# CAN.net
KiCad netlist of a schematic drawn in Altium Designer
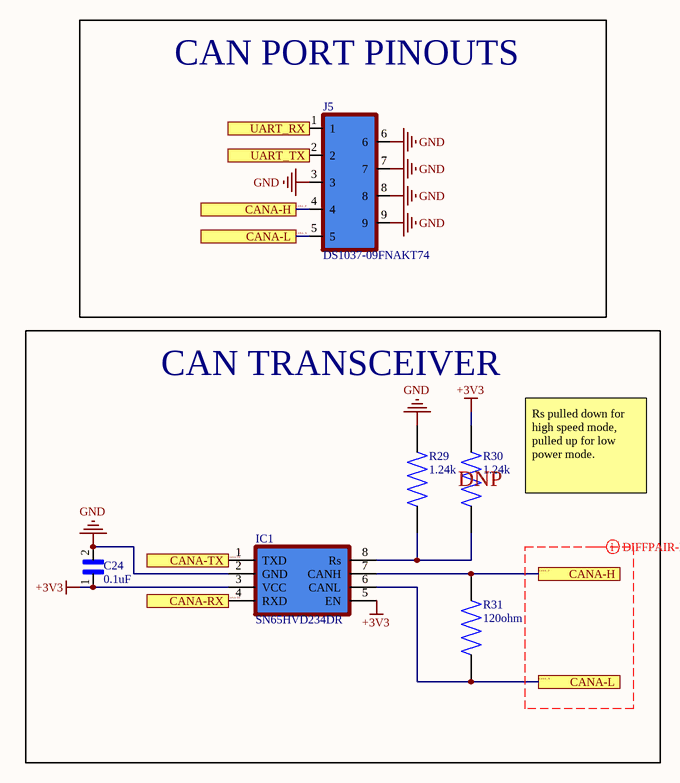
[diagram p0: CAN.SchDoc]

(export (version "E")
  (design (tool "Eeschema 10.0.6"))
  (components
    (comp (ref "C24")
      (value "0.1uF")
      (footprint "CAP 0805(2012 metric)")
      (description "0.1µF ±10% 25V Ceramic Capacitor X7R 0805 (2012Metric)")
      (libsource (lib "0.1uF 25V 0805") (part "0.1uF 25V 0805"))
    )
    (comp (ref "IC1")
      (value "SN65HVD234DR")
      (footprint "SN65HVD234DR")
      (libsource (lib "SN65HVD234DR") (part "SN65HVD234DR"))
    )
    (comp (ref "J5")
      (value "DS1037-09FNAKT74")
      (footprint "DSUB CONN 9 POS")
      (libsource (lib "DSUB CONN 9 POS") (part "DSBU CONN 9 POS"))
    )
    (comp (ref "R29")
      (value "1.24k")
      (footprint "RES 0805(2012 metric)")
      (description "1.24k 0805")
      (libsource (lib "1.24k 0805") (part "1.24k 0805"))
    )
    (comp (ref "R30")
      (value "1.24k")
      (footprint "RES 0805(2012 metric)")
      (description "1.24k 0805")
      (libsource (lib "1.24k 0805") (part "1.24k 0805"))
    )
    (comp (ref "R31")
      (value "120ohm")
      (footprint "RES 0805(2012 metric)")
      (description "120 Ohms ±5% 0.1W, 1/10W Chip Resistor 0805 (2012 Metric) Moisture Resistant Thick Film")
      (libsource (lib "120ohm 0805") (part "120ohm 0805"))
    )
  )
  (nets
    (net (code "1") (name "+3V3") (class "Default")
      (node (ref "C24") (pin "1") (pinfunction "1_1") (pintype "passive"))
      (node (ref "IC1") (pin "3") (pinfunction "VCC_3") (pintype "passive"))
      (node (ref "IC1") (pin "5") (pinfunction "EN_5") (pintype "passive"))
      (node (ref "R30") (pin "2") (pinfunction "2_2") (pintype "passive"))
    )
    (net (code "2") (name "/CANA-RX") (class "Default")
      (node (ref "IC1") (pin "4") (pinfunction "RXD_4") (pintype "passive"))
    )
    (net (code "3") (name "/CANA-TX") (class "Default")
      (node (ref "IC1") (pin "1") (pinfunction "TXD_1") (pintype "passive"))
    )
    (net (code "4") (name "/CANA_N") (class "Default")
      (node (ref "IC1") (pin "6") (pinfunction "CANL_6") (pintype "passive"))
      (node (ref "J5") (pin "5") (pinfunction "5_5") (pintype "passive"))
      (node (ref "R31") (pin "1") (pinfunction "1_1") (pintype "passive"))
    )
    (net (code "5") (name "/CANA_P") (class "Default")
      (node (ref "IC1") (pin "7") (pinfunction "CANH_7") (pintype "passive"))
      (node (ref "J5") (pin "4") (pinfunction "4_4") (pintype "passive"))
      (node (ref "R31") (pin "2") (pinfunction "2_2") (pintype "passive"))
    )
    (net (code "6") (name "/UART_RX") (class "Default")
      (node (ref "J5") (pin "1") (pinfunction "1_1") (pintype "passive"))
    )
    (net (code "7") (name "/UART_TX") (class "Default")
      (node (ref "J5") (pin "2") (pinfunction "2_2") (pintype "passive"))
    )
    (net (code "8") (name "GND") (class "Default")
      (node (ref "C24") (pin "2") (pinfunction "2_2") (pintype "passive"))
      (node (ref "IC1") (pin "2") (pinfunction "GND_2") (pintype "passive"))
      (node (ref "J5") (pin "3") (pinfunction "3_3") (pintype "passive"))
      (node (ref "J5") (pin "6") (pinfunction "6_6") (pintype "passive"))
      (node (ref "J5") (pin "7") (pinfunction "7_7") (pintype "passive"))
      (node (ref "J5") (pin "8") (pinfunction "8_8") (pintype "passive"))
      (node (ref "J5") (pin "9") (pinfunction "9_9") (pintype "passive"))
      (node (ref "R29") (pin "2") (pinfunction "2_2") (pintype "passive"))
    )
    (net (code "9") (name "Net-(IC1-Rs)") (class "Default")
      (node (ref "IC1") (pin "8") (pinfunction "Rs_8") (pintype "passive"))
      (node (ref "R29") (pin "1") (pinfunction "1_1") (pintype "passive"))
      (node (ref "R30") (pin "1") (pinfunction "1_1") (pintype "passive"))
    )
  )
)
